# Power-Supplies.net
KiCad netlist of a schematic drawn in Altium Designer
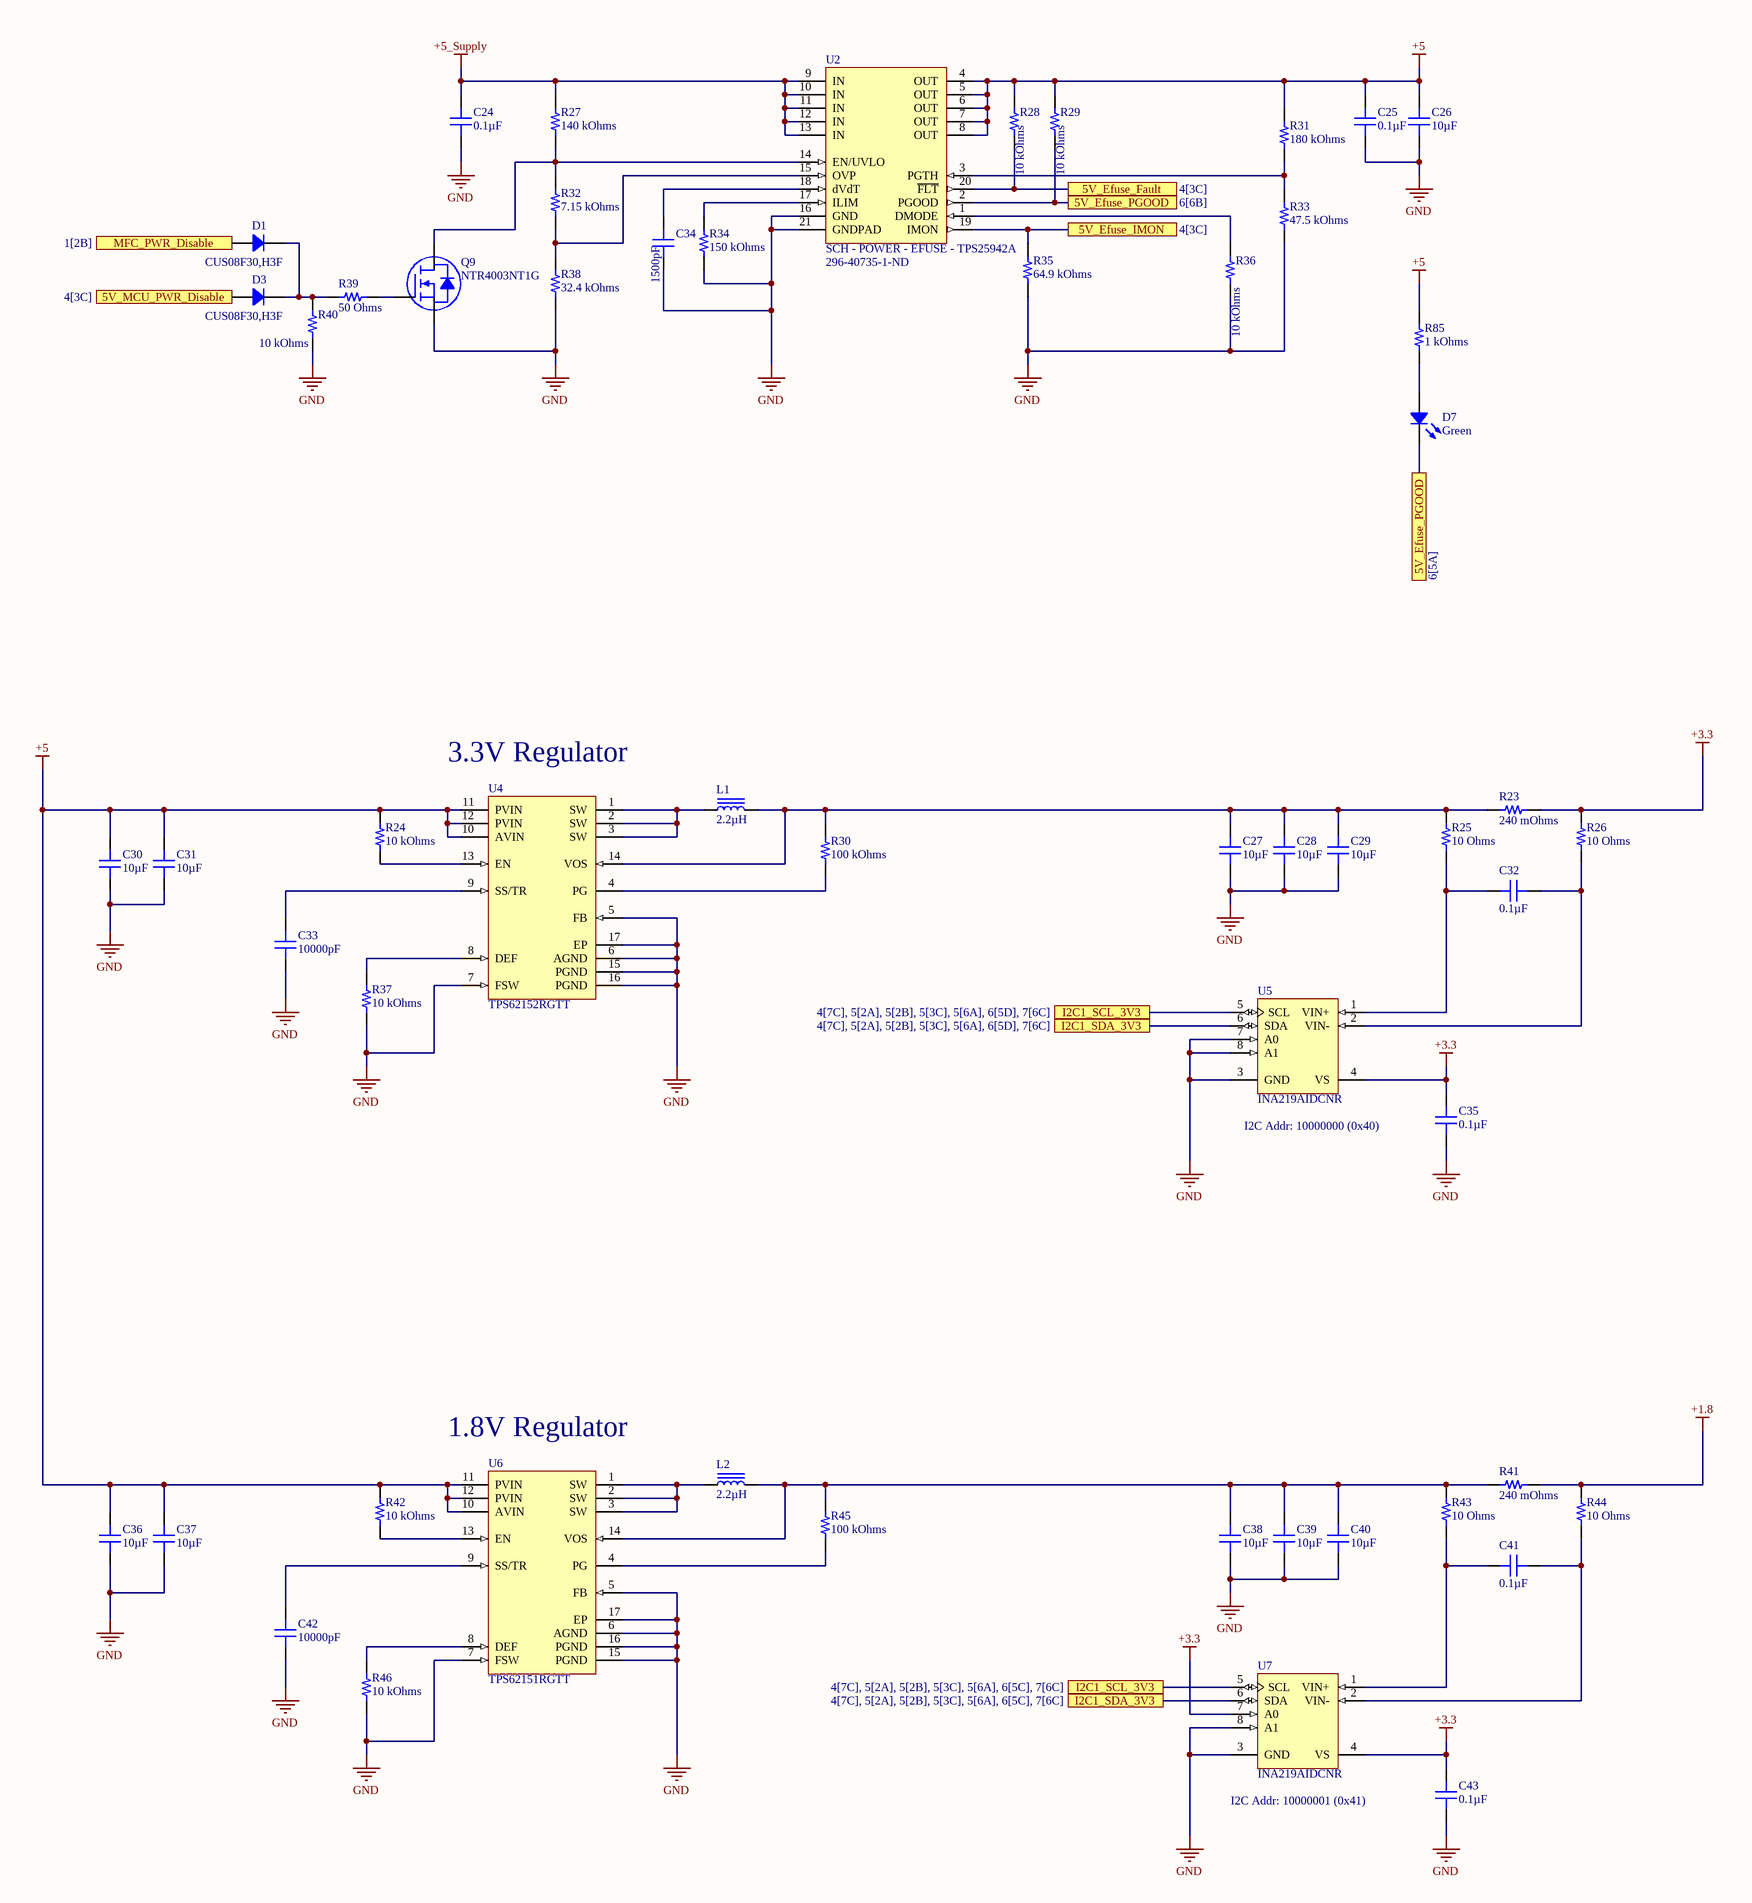
[diagram p0: Power-Supplies.SchDoc]

(export (version "E")
  (design (tool "Eeschema 10.0.6"))
  (components
    (comp (ref "C24")
      (value "0.1µF")
      (footprint "CAP 0603_1608")
      (description "CAP CER 0.1UF 25V X7R 0603")
      (fields
        (field (name "PART NUMBER") "CL10B104KA8WPNC")
        (field (name "MANUFACTURER") "Samsung Electro-Mechanics")
      )
      (libsource (lib "Celestial Altium Library - altium_library") (part "Capacitor"))
    )
    (comp (ref "C25")
      (value "0.1µF")
      (footprint "CAP 0603_1608")
      (description "CAP CER 0.1UF 25V X7R 0603")
      (fields
        (field (name "PART NUMBER") "CL10B104KA8WPNC")
        (field (name "MANUFACTURER") "Samsung Electro-Mechanics")
      )
      (libsource (lib "Celestial Altium Library - altium_library") (part "Capacitor"))
    )
    (comp (ref "C26")
      (value "10µF")
      (footprint "CAP 0805_2012")
      (description "CAP CER 10UF 16V X5R 0805")
      (fields (field (name "PART NUMBER") "CC0805KKX5R7BB106") (field (name "MANUFACTURER") "Yageo"))
      (libsource (lib "Celestial Altium Library - altium_library") (part "Capacitor"))
    )
    (comp (ref "C27")
      (value "10µF")
      (footprint "CAP 0805_2012")
      (description "CAP CER 10UF 16V X5R 0805")
      (fields (field (name "PART NUMBER") "CC0805KKX5R7BB106") (field (name "MANUFACTURER") "Yageo"))
      (libsource (lib "Celestial Altium Library - altium_library") (part "Capacitor"))
    )
    (comp (ref "C28")
      (value "10µF")
      (footprint "CAP 0805_2012")
      (description "CAP CER 10UF 16V X5R 0805")
      (fields (field (name "PART NUMBER") "CC0805KKX5R7BB106") (field (name "MANUFACTURER") "Yageo"))
      (libsource (lib "Celestial Altium Library - altium_library") (part "Capacitor"))
    )
    (comp (ref "C29")
      (value "10µF")
      (footprint "CAP 0805_2012")
      (description "CAP CER 10UF 16V X5R 0805")
      (fields (field (name "PART NUMBER") "CC0805KKX5R7BB106") (field (name "MANUFACTURER") "Yageo"))
      (libsource (lib "Celestial Altium Library - altium_library") (part "Capacitor"))
    )
    (comp (ref "C30")
      (value "10µF")
      (footprint "CAP 0805_2012")
      (description "CAP CER 10UF 16V X5R 0805")
      (fields (field (name "PART NUMBER") "CC0805KKX5R7BB106") (field (name "MANUFACTURER") "Yageo"))
      (libsource (lib "Celestial Altium Library - altium_library") (part "Capacitor"))
    )
    (comp (ref "C31")
      (value "10µF")
      (footprint "CAP 0805_2012")
      (description "CAP CER 10UF 16V X5R 0805")
      (fields (field (name "PART NUMBER") "CC0805KKX5R7BB106") (field (name "MANUFACTURER") "Yageo"))
      (libsource (lib "Celestial Altium Library - altium_library") (part "Capacitor"))
    )
    (comp (ref "C32")
      (value "0.1µF")
      (footprint "CAP 0603_1608")
      (description "CAP CER 0.1UF 25V X7R 0603")
      (fields
        (field (name "PART NUMBER") "CL10B104KA8WPNC")
        (field (name "MANUFACTURER") "Samsung Electro-Mechanics")
      )
      (libsource (lib "Celestial Altium Library - altium_library") (part "Capacitor"))
    )
    (comp (ref "C33")
      (value "10000pF")
      (footprint "CAP 0603_1608")
      (description "CAP CER 10000PF 16V X7R 0603")
      (fields (field (name "PART NUMBER") "C0603S103K4RACTU") (field (name "MANUFACTURER") "KEMET"))
      (libsource (lib "Celestial Altium Library - altium_library") (part "Capacitor"))
    )
    (comp (ref "C34")
      (value "1500pF")
      (footprint "CAP 0603_1608")
      (description "CAP CER 1500PF 25V X7R 0603")
      (fields (field (name "PART NUMBER") "CC0603JRX7R8BB152") (field (name "MANUFACTURER") "Yageo"))
      (libsource (lib "Celestial Altium Library - altium_library") (part "Capacitor"))
    )
    (comp (ref "C35")
      (value "0.1µF")
      (footprint "CAP 0603_1608")
      (description "CAP CER 0.1UF 25V X7R 0603")
      (fields
        (field (name "PART NUMBER") "CL10B104KA8WPNC")
        (field (name "MANUFACTURER") "Samsung Electro-Mechanics")
      )
      (libsource (lib "Celestial Altium Library - altium_library") (part "Capacitor"))
    )
    (comp (ref "C36")
      (value "10µF")
      (footprint "CAP 0805_2012")
      (description "CAP CER 10UF 16V X5R 0805")
      (fields (field (name "PART NUMBER") "CC0805KKX5R7BB106") (field (name "MANUFACTURER") "Yageo"))
      (libsource (lib "Celestial Altium Library - altium_library") (part "Capacitor"))
    )
    (comp (ref "C37")
      (value "10µF")
      (footprint "CAP 0805_2012")
      (description "CAP CER 10UF 16V X5R 0805")
      (fields (field (name "PART NUMBER") "CC0805KKX5R7BB106") (field (name "MANUFACTURER") "Yageo"))
      (libsource (lib "Celestial Altium Library - altium_library") (part "Capacitor"))
    )
    (comp (ref "C38")
      (value "10µF")
      (footprint "CAP 0805_2012")
      (description "CAP CER 10UF 16V X5R 0805")
      (fields (field (name "PART NUMBER") "CC0805KKX5R7BB106") (field (name "MANUFACTURER") "Yageo"))
      (libsource (lib "Celestial Altium Library - altium_library") (part "Capacitor"))
    )
    (comp (ref "C39")
      (value "10µF")
      (footprint "CAP 0805_2012")
      (description "CAP CER 10UF 16V X5R 0805")
      (fields (field (name "PART NUMBER") "CC0805KKX5R7BB106") (field (name "MANUFACTURER") "Yageo"))
      (libsource (lib "Celestial Altium Library - altium_library") (part "Capacitor"))
    )
    (comp (ref "C40")
      (value "10µF")
      (footprint "CAP 0805_2012")
      (description "CAP CER 10UF 16V X5R 0805")
      (fields (field (name "PART NUMBER") "CC0805KKX5R7BB106") (field (name "MANUFACTURER") "Yageo"))
      (libsource (lib "Celestial Altium Library - altium_library") (part "Capacitor"))
    )
    (comp (ref "C41")
      (value "0.1µF")
      (footprint "CAP 0603_1608")
      (description "CAP CER 0.1UF 25V X7R 0603")
      (fields
        (field (name "PART NUMBER") "CL10B104KA8WPNC")
        (field (name "MANUFACTURER") "Samsung Electro-Mechanics")
      )
      (libsource (lib "Celestial Altium Library - altium_library") (part "Capacitor"))
    )
    (comp (ref "C42")
      (value "10000pF")
      (footprint "CAP 0603_1608")
      (description "CAP CER 10000PF 16V X7R 0603")
      (fields (field (name "PART NUMBER") "C0603S103K4RACTU") (field (name "MANUFACTURER") "KEMET"))
      (libsource (lib "Celestial Altium Library - altium_library") (part "Capacitor"))
    )
    (comp (ref "C43")
      (value "0.1µF")
      (footprint "CAP 0603_1608")
      (description "CAP CER 0.1UF 25V X7R 0603")
      (fields
        (field (name "PART NUMBER") "CL10B104KA8WPNC")
        (field (name "MANUFACTURER") "Samsung Electro-Mechanics")
      )
      (libsource (lib "Celestial Altium Library - altium_library") (part "Capacitor"))
    )
    (comp (ref "D1")
      (value "CUS08F30,H3F")
      (footprint "SOD323")
      (description "DIODE SCHOTTKY 30V 800MA USC")
      (fields (field (name "MANUFACTURER") "Toshiba Semiconductor and Storage"))
      (libsource (lib "Celestial Altium Library - altium_library") (part "Diode"))
    )
    (comp (ref "D3")
      (value "CUS08F30,H3F")
      (footprint "SOD323")
      (description "DIODE SCHOTTKY 30V 800MA USC")
      (fields (field (name "MANUFACTURER") "Toshiba Semiconductor and Storage"))
      (libsource (lib "Celestial Altium Library - altium_library") (part "Diode"))
    )
    (comp (ref "D7")
      (value "Green")
      (footprint "LED 0603_1608 GREEN")
      (description "LED GREEN CLEAR CHIP SMD")
      (fields (field (name "PART NUMBER") "LTST-C193KGKT-5A") (field (name "MANUFACTURER") "Lite-On Inc."))
      (libsource (lib "Celestial Altium Library - altium_library") (part "LED"))
    )
    (comp (ref "L1")
      (value "2.2µH")
      (footprint "BOURNS SRN4018")
      (description "FIXED IND 2.2UH 2.9A 44 MOHM SMD")
      (fields (field (name "PART NUMBER") "SRN4018-2R2M") (field (name "MANUFACTURER") "Bourns Inc."))
      (libsource (lib "Celestial Altium Library - altium_library") (part "Inductor"))
    )
    (comp (ref "L2")
      (value "2.2µH")
      (footprint "BOURNS SRN4018")
      (description "FIXED IND 2.2UH 2.9A 44 MOHM SMD")
      (fields (field (name "PART NUMBER") "SRN4018-2R2M") (field (name "MANUFACTURER") "Bourns Inc."))
      (libsource (lib "Celestial Altium Library - altium_library") (part "Inductor"))
    )
    (comp (ref "Q9")
      (value "NTR4003NT1G")
      (footprint "ON SEMI SOT-23-3")
      (description "MOSFET N-CH 30V 500MA SOT-23")
      (fields (field (name "MANUFACTURER") "ON Semiconductor"))
      (libsource (lib "Celestial Altium Library - altium_library") (part "ON SEMI MOSFET N-CH SOT-23-3"))
    )
    (comp (ref "R23")
      (value "240 mOhms")
      (footprint "RES 0805_2012")
      (description "RES 0.24 OHM 1% 1/2W 0805")
      (fields
        (field (name "PART NUMBER") "ERJ-6DQFR24V")
        (field (name "MANUFACTURER") "Panasonic Electronic Components")
      )
      (libsource (lib "Celestial Altium Library - altium_library") (part "Resistor"))
    )
    (comp (ref "R24")
      (value "10 kOhms")
      (footprint "RES 0603_1608")
      (description "RES 10K OHM 5% 1/10W 0603")
      (fields
        (field (name "PART NUMBER") "RMCF0603JT10K0")
        (field (name "MANUFACTURER") "Stackpole Electronics Inc")
      )
      (libsource (lib "Celestial Altium Library - altium_library") (part "Resistor"))
    )
    (comp (ref "R25")
      (value "10 Ohms")
      (footprint "RES 0603_1608")
      (description "CRGCQ 0603 10R 1%")
      (fields
        (field (name "PART NUMBER") "CRGCQ0603F10R")
        (field (name "MANUFACTURER") "TE Connectivity Passive Product")
      )
      (libsource (lib "Celestial Altium Library - altium_library") (part "Resistor"))
    )
    (comp (ref "R26")
      (value "10 Ohms")
      (footprint "RES 0603_1608")
      (description "CRGCQ 0603 10R 1%")
      (fields
        (field (name "PART NUMBER") "CRGCQ0603F10R")
        (field (name "MANUFACTURER") "TE Connectivity Passive Product")
      )
      (libsource (lib "Celestial Altium Library - altium_library") (part "Resistor"))
    )
    (comp (ref "R27")
      (value "140 kOhms")
      (footprint "RES 0603_1608")
      (description "RES SMD 140K OHM 0.1% 1/10W 0603")
      (fields (field (name "PART NUMBER") "RT0603BRE07140KL") (field (name "MANUFACTURER") "Yageo"))
      (libsource (lib "Celestial Altium Library - altium_library") (part "Resistor"))
    )
    (comp (ref "R28")
      (value "10 kOhms")
      (footprint "RES 0603_1608")
      (description "RES 10K OHM 5% 1/10W 0603")
      (fields
        (field (name "PART NUMBER") "RMCF0603JT10K0")
        (field (name "MANUFACTURER") "Stackpole Electronics Inc")
      )
      (libsource (lib "Celestial Altium Library - altium_library") (part "Resistor"))
    )
    (comp (ref "R29")
      (value "10 kOhms")
      (footprint "RES 0603_1608")
      (description "RES 10K OHM 5% 1/10W 0603")
      (fields
        (field (name "PART NUMBER") "RMCF0603JT10K0")
        (field (name "MANUFACTURER") "Stackpole Electronics Inc")
      )
      (libsource (lib "Celestial Altium Library - altium_library") (part "Resistor"))
    )
    (comp (ref "R30")
      (value "100 kOhms")
      (footprint "RES 0603_1608")
      (description "RES SMD 100K OHM 5% 1/10W 0603")
      (fields (field (name "PART NUMBER") "RC0603JR-10100KL") (field (name "MANUFACTURER") "Yageo"))
      (libsource (lib "Celestial Altium Library - altium_library") (part "Resistor"))
    )
    (comp (ref "R31")
      (value "180 kOhms")
      (footprint "RES 0603_1608")
      (description "RES 180K OHM 1% 1/10W 0603")
      (fields
        (field (name "PART NUMBER") "RMCF0603FT180K")
        (field (name "MANUFACTURER") "Stackpole Electronics Inc")
      )
      (libsource (lib "Celestial Altium Library - altium_library") (part "Resistor"))
    )
    (comp (ref "R32")
      (value "7.15 kOhms")
      (footprint "RES 0603_1608")
      (description "RES SMD 7.15K OHM 0.1% 1/5W 0603")
      (fields
        (field (name "PART NUMBER") "ERJ-PB3B7151V")
        (field (name "MANUFACTURER") "Panasonic Electronic Components")
      )
      (libsource (lib "Celestial Altium Library - altium_library") (part "Resistor"))
    )
    (comp (ref "R33")
      (value "47.5 kOhms")
      (footprint "RES 0603_1608")
      (description "RES 47.5K OHM 1% 1/10W 0603")
      (fields
        (field (name "PART NUMBER") "RMCF0603FG47K5")
        (field (name "MANUFACTURER") "Stackpole Electronics Inc")
      )
      (libsource (lib "Celestial Altium Library - altium_library") (part "Resistor"))
    )
    (comp (ref "R34")
      (value "150 kOhms")
      (footprint "RES 0603_1608")
      (description "RES 150K OHM 1% 1/10W 0603")
      (fields
        (field (name "PART NUMBER") "RMCF0603FG150K")
        (field (name "MANUFACTURER") "Stackpole Electronics Inc")
      )
      (libsource (lib "Celestial Altium Library - altium_library") (part "Resistor"))
    )
    (comp (ref "R35")
      (value "64.9 kOhms")
      (footprint "RES 0603_1608")
      (description "RES 64.9K OHM 1% 1/10W 0603")
      (fields
        (field (name "PART NUMBER") "RMCF0603FT64K9")
        (field (name "MANUFACTURER") "Stackpole Electronics Inc")
      )
      (libsource (lib "Celestial Altium Library - altium_library") (part "Resistor"))
    )
    (comp (ref "R36")
      (value "10 kOhms")
      (footprint "RES 0603_1608")
      (description "RES 10K OHM 5% 1/10W 0603")
      (fields
        (field (name "PART NUMBER") "RMCF0603JT10K0")
        (field (name "MANUFACTURER") "Stackpole Electronics Inc")
      )
      (libsource (lib "Celestial Altium Library - altium_library") (part "Resistor"))
    )
    (comp (ref "R37")
      (value "10 kOhms")
      (footprint "RES 0603_1608")
      (description "RES 10K OHM 5% 1/10W 0603")
      (fields
        (field (name "PART NUMBER") "RMCF0603JT10K0")
        (field (name "MANUFACTURER") "Stackpole Electronics Inc")
      )
      (libsource (lib "Celestial Altium Library - altium_library") (part "Resistor"))
    )
    (comp (ref "R38")
      (value "32.4 kOhms")
      (footprint "RES 0603_1608")
      (description "RES SMD 32.4K OHM 0.1% 1/5W 0603")
      (fields
        (field (name "PART NUMBER") "ERJ-PB3B3242V")
        (field (name "MANUFACTURER") "Panasonic Electronic Components")
      )
      (libsource (lib "Celestial Altium Library - altium_library") (part "Resistor"))
    )
    (comp (ref "R39")
      (value "50 Ohms")
      (footprint "RES 0603_1608")
      (description "RES SMD 50 OHM 1% 1/10W 0603")
      (fields (field (name "PART NUMBER") "CRCW060350R0FKEA") (field (name "MANUFACTURER") "Vishay Dale"))
      (libsource (lib "Celestial Altium Library - altium_library") (part "Resistor"))
    )
    (comp (ref "R40")
      (value "10 kOhms")
      (footprint "RES 0603_1608")
      (description "RES 10K OHM 5% 1/10W 0603")
      (fields
        (field (name "PART NUMBER") "RMCF0603JT10K0")
        (field (name "MANUFACTURER") "Stackpole Electronics Inc")
      )
      (libsource (lib "Celestial Altium Library - altium_library") (part "Resistor"))
    )
    (comp (ref "R41")
      (value "240 mOhms")
      (footprint "RES 0805_2012")
      (description "RES 0.24 OHM 1% 1/2W 0805")
      (fields
        (field (name "PART NUMBER") "ERJ-6DQFR24V")
        (field (name "MANUFACTURER") "Panasonic Electronic Components")
      )
      (libsource (lib "Celestial Altium Library - altium_library") (part "Resistor"))
    )
    (comp (ref "R42")
      (value "10 kOhms")
      (footprint "RES 0603_1608")
      (description "RES 10K OHM 5% 1/10W 0603")
      (fields
        (field (name "PART NUMBER") "RMCF0603JT10K0")
        (field (name "MANUFACTURER") "Stackpole Electronics Inc")
      )
      (libsource (lib "Celestial Altium Library - altium_library") (part "Resistor"))
    )
    (comp (ref "R43")
      (value "10 Ohms")
      (footprint "RES 0603_1608")
      (description "CRGCQ 0603 10R 1%")
      (fields
        (field (name "PART NUMBER") "CRGCQ0603F10R")
        (field (name "MANUFACTURER") "TE Connectivity Passive Product")
      )
      (libsource (lib "Celestial Altium Library - altium_library") (part "Resistor"))
    )
    (comp (ref "R44")
      (value "10 Ohms")
      (footprint "RES 0603_1608")
      (description "CRGCQ 0603 10R 1%")
      (fields
        (field (name "PART NUMBER") "CRGCQ0603F10R")
        (field (name "MANUFACTURER") "TE Connectivity Passive Product")
      )
      (libsource (lib "Celestial Altium Library - altium_library") (part "Resistor"))
    )
    (comp (ref "R45")
      (value "100 kOhms")
      (footprint "RES 0603_1608")
      (description "RES SMD 100K OHM 5% 1/10W 0603")
      (fields (field (name "PART NUMBER") "RC0603JR-10100KL") (field (name "MANUFACTURER") "Yageo"))
      (libsource (lib "Celestial Altium Library - altium_library") (part "Resistor"))
    )
    (comp (ref "R46")
      (value "10 kOhms")
      (footprint "RES 0603_1608")
      (description "RES 10K OHM 5% 1/10W 0603")
      (fields
        (field (name "PART NUMBER") "RMCF0603JT10K0")
        (field (name "MANUFACTURER") "Stackpole Electronics Inc")
      )
      (libsource (lib "Celestial Altium Library - altium_library") (part "Resistor"))
    )
    (comp (ref "R85")
      (value "1 kOhms")
      (footprint "RES 0603_1608")
      (description "RES 1K OHM 1% 1/8W 0603")
      (fields
        (field (name "PART NUMBER") "RNCP0603FTD1K00")
        (field (name "MANUFACTURER") "Stackpole Electronics Inc")
      )
      (libsource (lib "Celestial Altium Library - altium_library") (part "Resistor"))
    )
    (comp (ref "U2")
      (value "SCH - POWER - EFUSE - TPS25942A")
      (footprint "PCB - LEADLESS - QFN - TI 20-WQFN")
      (fields (field (name "SUPPLIER PART NUMBER 1") "296-40735-1-ND"))
      (libsource (lib "HAB_ICs") (part "SCH - POWER - EFUSE - TPS25942A"))
    )
    (comp (ref "U4")
      (value "TPS62152RGTT")
      (footprint "RGT0016C_V")
      (fields (field (name "MANUFACTURER") "Texas Instruments"))
      (libsource (lib "Altium Content Vault") (part "TI-TPS62152RGT16-1700X1700TP"))
    )
    (comp (ref "U5")
      (value "INA219AIDCNR")
      (footprint "DCN0008A_M")
      (fields (field (name "MANUFACTURER") "Texas Instruments"))
      (libsource (lib "Altium Content Vault") (part "TI-INA219DCN8"))
    )
    (comp (ref "U6")
      (value "TPS62151RGTT")
      (footprint "RGT0016C_V")
      (fields (field (name "MANUFACTURER") "Texas Instruments"))
      (libsource (lib "Altium Content Vault") (part "TI-TPS62151RGT16-1700X1700TP"))
    )
    (comp (ref "U7")
      (value "INA219AIDCNR")
      (footprint "DCN0008A_M")
      (fields (field (name "MANUFACTURER") "Texas Instruments"))
      (libsource (lib "Altium Content Vault") (part "TI-INA219DCN8"))
    )
  )
  (nets
    (net (code "1") (name "+1.8") (class "Default")
      (node (ref "R41") (pin "2") (pinfunction "2_2") (pintype "passive"))
      (node (ref "R44") (pin "2") (pinfunction "2_2") (pintype "passive"))
    )
    (net (code "2") (name "+3.3") (class "Default")
      (node (ref "C35") (pin "2") (pinfunction "2_2") (pintype "passive"))
      (node (ref "C43") (pin "2") (pinfunction "2_2") (pintype "passive"))
      (node (ref "R23") (pin "2") (pinfunction "2_2") (pintype "passive"))
      (node (ref "R26") (pin "2") (pinfunction "2_2") (pintype "passive"))
      (node (ref "U5") (pin "4") (pinfunction "VS_4") (pintype "power_in"))
      (node (ref "U7") (pin "4") (pinfunction "VS_4") (pintype "power_in"))
      (node (ref "U7") (pin "7") (pinfunction "A0_7") (pintype "input"))
    )
    (net (code "3") (name "+5") (class "Default")
      (node (ref "C25") (pin "2") (pinfunction "2_2") (pintype "passive"))
      (node (ref "C26") (pin "2") (pinfunction "2_2") (pintype "passive"))
      (node (ref "C30") (pin "2") (pinfunction "2_2") (pintype "passive"))
      (node (ref "C31") (pin "2") (pinfunction "2_2") (pintype "passive"))
      (node (ref "C36") (pin "2") (pinfunction "2_2") (pintype "passive"))
      (node (ref "C37") (pin "2") (pinfunction "2_2") (pintype "passive"))
      (node (ref "R24") (pin "2") (pinfunction "2_2") (pintype "passive"))
      (node (ref "R28") (pin "2") (pinfunction "2_2") (pintype "passive"))
      (node (ref "R29") (pin "2") (pinfunction "2_2") (pintype "passive"))
      (node (ref "R31") (pin "2") (pinfunction "2_2") (pintype "passive"))
      (node (ref "R42") (pin "2") (pinfunction "2_2") (pintype "passive"))
      (node (ref "R85") (pin "1") (pinfunction "1_1") (pintype "passive"))
      (node (ref "U2") (pin "4") (pinfunction "OUT_4") (pintype "power_in"))
      (node (ref "U2") (pin "5") (pinfunction "OUT_5") (pintype "power_in"))
      (node (ref "U2") (pin "6") (pinfunction "OUT_6") (pintype "power_in"))
      (node (ref "U2") (pin "7") (pinfunction "OUT_7") (pintype "power_in"))
      (node (ref "U2") (pin "8") (pinfunction "OUT_8") (pintype "power_in"))
      (node (ref "U4") (pin "10") (pinfunction "AVIN_10") (pintype "power_in"))
      (node (ref "U4") (pin "11") (pinfunction "PVIN_11") (pintype "power_in"))
      (node (ref "U4") (pin "12") (pinfunction "PVIN_12") (pintype "power_in"))
      (node (ref "U6") (pin "10") (pinfunction "AVIN_10") (pintype "power_in"))
      (node (ref "U6") (pin "11") (pinfunction "PVIN_11") (pintype "power_in"))
      (node (ref "U6") (pin "12") (pinfunction "PVIN_12") (pintype "power_in"))
    )
    (net (code "4") (name "+5_Supply") (class "Default")
      (node (ref "C24") (pin "2") (pinfunction "2_2") (pintype "passive"))
      (node (ref "R27") (pin "2") (pinfunction "2_2") (pintype "passive"))
      (node (ref "U2") (pin "10") (pinfunction "IN_10") (pintype "power_in"))
      (node (ref "U2") (pin "11") (pinfunction "IN_11") (pintype "power_in"))
      (node (ref "U2") (pin "12") (pinfunction "IN_12") (pintype "power_in"))
      (node (ref "U2") (pin "13") (pinfunction "IN_13") (pintype "power_in"))
      (node (ref "U2") (pin "9") (pinfunction "IN_9") (pintype "power_in"))
    )
    (net (code "5") (name "/5V_Efuse_Fault") (class "Default")
      (node (ref "R28") (pin "1") (pinfunction "1_1") (pintype "passive"))
      (node (ref "U2") (pin "20") (pinfunction "~{FLT}_20") (pintype "output"))
    )
    (net (code "6") (name "/5V_Efuse_IMON") (class "Default")
      (node (ref "R35") (pin "2") (pinfunction "2_2") (pintype "passive"))
      (node (ref "U2") (pin "19") (pinfunction "IMON_19") (pintype "output"))
    )
    (net (code "7") (name "/5V_Efuse_PGOOD") (class "Default")
      (node (ref "D7") (pin "2") (pinfunction "2_2") (pintype "passive"))
      (node (ref "R29") (pin "1") (pinfunction "1_1") (pintype "passive"))
      (node (ref "U2") (pin "2") (pinfunction "PGOOD_2") (pintype "output"))
    )
    (net (code "8") (name "/5V_MCU_PWR_Disable") (class "Default")
      (node (ref "D3") (pin "1") (pinfunction "1_1") (pintype "passive"))
    )
    (net (code "9") (name "/I2C1_SCL_3V3") (class "Default")
      (node (ref "U5") (pin "5") (pinfunction "SCL_5") (pintype "bidirectional"))
      (node (ref "U7") (pin "5") (pinfunction "SCL_5") (pintype "bidirectional"))
    )
    (net (code "10") (name "/I2C1_SDA_3V3") (class "Default")
      (node (ref "U5") (pin "6") (pinfunction "SDA_6") (pintype "bidirectional"))
      (node (ref "U7") (pin "6") (pinfunction "SDA_6") (pintype "bidirectional"))
    )
    (net (code "11") (name "/MFC_PWR_Disable") (class "Default")
      (node (ref "D1") (pin "1") (pinfunction "1_1") (pintype "passive"))
    )
    (net (code "12") (name "GND") (class "Default")
      (node (ref "C24") (pin "1") (pinfunction "1_1") (pintype "passive"))
      (node (ref "C25") (pin "1") (pinfunction "1_1") (pintype "passive"))
      (node (ref "C26") (pin "1") (pinfunction "1_1") (pintype "passive"))
      (node (ref "C27") (pin "1") (pinfunction "1_1") (pintype "passive"))
      (node (ref "C28") (pin "1") (pinfunction "1_1") (pintype "passive"))
      (node (ref "C29") (pin "1") (pinfunction "1_1") (pintype "passive"))
      (node (ref "C30") (pin "1") (pinfunction "1_1") (pintype "passive"))
      (node (ref "C31") (pin "1") (pinfunction "1_1") (pintype "passive"))
      (node (ref "C33") (pin "1") (pinfunction "1_1") (pintype "passive"))
      (node (ref "C34") (pin "1") (pinfunction "1_1") (pintype "passive"))
      (node (ref "C35") (pin "1") (pinfunction "1_1") (pintype "passive"))
      (node (ref "C36") (pin "1") (pinfunction "1_1") (pintype "passive"))
      (node (ref "C37") (pin "1") (pinfunction "1_1") (pintype "passive"))
      (node (ref "C38") (pin "1") (pinfunction "1_1") (pintype "passive"))
      (node (ref "C39") (pin "1") (pinfunction "1_1") (pintype "passive"))
      (node (ref "C40") (pin "1") (pinfunction "1_1") (pintype "passive"))
      (node (ref "C42") (pin "1") (pinfunction "1_1") (pintype "passive"))
      (node (ref "C43") (pin "1") (pinfunction "1_1") (pintype "passive"))
      (node (ref "Q9") (pin "2") (pinfunction "S_2") (pintype "passive"))
      (node (ref "R33") (pin "1") (pinfunction "1_1") (pintype "passive"))
      (node (ref "R34") (pin "1") (pinfunction "1_1") (pintype "passive"))
      (node (ref "R35") (pin "1") (pinfunction "1_1") (pintype "passive"))
      (node (ref "R36") (pin "1") (pinfunction "1_1") (pintype "passive"))
      (node (ref "R37") (pin "1") (pinfunction "1_1") (pintype "passive"))
      (node (ref "R38") (pin "1") (pinfunction "1_1") (pintype "passive"))
      (node (ref "R40") (pin "1") (pinfunction "1_1") (pintype "passive"))
      (node (ref "R46") (pin "1") (pinfunction "1_1") (pintype "passive"))
      (node (ref "U2") (pin "16") (pinfunction "GND_16") (pintype "power_in"))
      (node (ref "U2") (pin "21") (pinfunction "GNDPAD_21") (pintype "power_in"))
      (node (ref "U4") (pin "15") (pinfunction "PGND_15") (pintype "power_in"))
      (node (ref "U4") (pin "16") (pinfunction "PGND_16") (pintype "power_in"))
      (node (ref "U4") (pin "17") (pinfunction "EP_17") (pintype "power_in"))
      (node (ref "U4") (pin "5") (pinfunction "FB_5") (pintype "input"))
      (node (ref "U4") (pin "6") (pinfunction "AGND_6") (pintype "power_in"))
      (node (ref "U4") (pin "7") (pinfunction "FSW_7") (pintype "input"))
      (node (ref "U5") (pin "3") (pinfunction "GND_3") (pintype "power_in"))
      (node (ref "U5") (pin "7") (pinfunction "A0_7") (pintype "input"))
      (node (ref "U5") (pin "8") (pinfunction "A1_8") (pintype "input"))
      (node (ref "U6") (pin "15") (pinfunction "PGND_15") (pintype "power_in"))
      (node (ref "U6") (pin "16") (pinfunction "PGND_16") (pintype "power_in"))
      (node (ref "U6") (pin "17") (pinfunction "EP_17") (pintype "power_in"))
      (node (ref "U6") (pin "5") (pinfunction "FB_5") (pintype "input"))
      (node (ref "U6") (pin "6") (pinfunction "AGND_6") (pintype "power_in"))
      (node (ref "U6") (pin "7") (pinfunction "FSW_7") (pintype "input"))
      (node (ref "U7") (pin "3") (pinfunction "GND_3") (pintype "power_in"))
      (node (ref "U7") (pin "8") (pinfunction "A1_8") (pintype "input"))
    )
    (net (code "13") (name "Net-(D1-Pad2)") (class "Default")
      (node (ref "D1") (pin "2") (pinfunction "2_2") (pintype "passive"))
      (node (ref "D3") (pin "2") (pinfunction "2_2") (pintype "passive"))
      (node (ref "R39") (pin "2") (pinfunction "2_2") (pintype "passive"))
      (node (ref "R40") (pin "2") (pinfunction "2_2") (pintype "passive"))
    )
    (net (code "14") (name "Net-(D7-Pad1)") (class "Default")
      (node (ref "D7") (pin "1") (pinfunction "1_1") (pintype "passive"))
      (node (ref "R85") (pin "2") (pinfunction "2_2") (pintype "passive"))
    )
    (net (code "15") (name "Net-(L1-Pad1)") (class "Default")
      (node (ref "L1") (pin "1") (pinfunction "1_1") (pintype "passive"))
      (node (ref "U4") (pin "1") (pinfunction "SW_1") (pintype "power_in"))
      (node (ref "U4") (pin "2") (pinfunction "SW_2") (pintype "power_in"))
      (node (ref "U4") (pin "3") (pinfunction "SW_3") (pintype "power_in"))
    )
    (net (code "16") (name "Net-(L2-Pad1)") (class "Default")
      (node (ref "L2") (pin "1") (pinfunction "1_1") (pintype "passive"))
      (node (ref "U6") (pin "1") (pinfunction "SW_1") (pintype "power_in"))
      (node (ref "U6") (pin "2") (pinfunction "SW_2") (pintype "power_in"))
      (node (ref "U6") (pin "3") (pinfunction "SW_3") (pintype "power_in"))
    )
    (net (code "17") (name "Net-(Q9-D)") (class "Default")
      (node (ref "Q9") (pin "3") (pinfunction "D_3") (pintype "passive"))
      (node (ref "R27") (pin "1") (pinfunction "1_1") (pintype "passive"))
      (node (ref "R32") (pin "2") (pinfunction "2_2") (pintype "passive"))
      (node (ref "U2") (pin "14") (pinfunction "EN/UVLO_14") (pintype "input"))
    )
    (net (code "18") (name "Net-(Q9-G)") (class "Default")
      (node (ref "Q9") (pin "1") (pinfunction "G_1") (pintype "passive"))
      (node (ref "R39") (pin "1") (pinfunction "1_1") (pintype "passive"))
    )
    (net (code "19") (name "Net-(U2-DMODE)") (class "Default")
      (node (ref "R36") (pin "2") (pinfunction "2_2") (pintype "passive"))
      (node (ref "U2") (pin "1") (pinfunction "DMODE_1") (pintype "input"))
    )
    (net (code "20") (name "Net-(U2-ILIM)") (class "Default")
      (node (ref "R34") (pin "2") (pinfunction "2_2") (pintype "passive"))
      (node (ref "U2") (pin "17") (pinfunction "ILIM_17") (pintype "input"))
    )
    (net (code "21") (name "Net-(U2-OVP)") (class "Default")
      (node (ref "R32") (pin "1") (pinfunction "1_1") (pintype "passive"))
      (node (ref "R38") (pin "2") (pinfunction "2_2") (pintype "passive"))
      (node (ref "U2") (pin "15") (pinfunction "OVP_15") (pintype "input"))
    )
    (net (code "22") (name "Net-(U2-PGTH)") (class "Default")
      (node (ref "R31") (pin "1") (pinfunction "1_1") (pintype "passive"))
      (node (ref "R33") (pin "2") (pinfunction "2_2") (pintype "passive"))
      (node (ref "U2") (pin "3") (pinfunction "PGTH_3") (pintype "input"))
    )
    (net (code "23") (name "Net-(U2-dVdT)") (class "Default")
      (node (ref "C34") (pin "2") (pinfunction "2_2") (pintype "passive"))
      (node (ref "U2") (pin "18") (pinfunction "dVdT_18") (pintype "input"))
    )
    (net (code "24") (name "Net-(U4-DEF)") (class "Default")
      (node (ref "R37") (pin "2") (pinfunction "2_2") (pintype "passive"))
      (node (ref "U4") (pin "8") (pinfunction "DEF_8") (pintype "input"))
    )
    (net (code "25") (name "Net-(U4-EN)") (class "Default")
      (node (ref "R24") (pin "1") (pinfunction "1_1") (pintype "passive"))
      (node (ref "U4") (pin "13") (pinfunction "EN_13") (pintype "input"))
    )
    (net (code "26") (name "Net-(U4-PG)") (class "Default")
      (node (ref "R30") (pin "1") (pinfunction "1_1") (pintype "passive"))
      (node (ref "U4") (pin "4") (pinfunction "PG_4") (pintype "tri_state"))
    )
    (net (code "27") (name "Net-(U4-SS{slash}TR)") (class "Default")
      (node (ref "C33") (pin "2") (pinfunction "2_2") (pintype "passive"))
      (node (ref "U4") (pin "9") (pinfunction "SS/TR_9") (pintype "input"))
    )
    (net (code "28") (name "Net-(U4-VOS)") (class "Default")
      (node (ref "C27") (pin "2") (pinfunction "2_2") (pintype "passive"))
      (node (ref "C28") (pin "2") (pinfunction "2_2") (pintype "passive"))
      (node (ref "C29") (pin "2") (pinfunction "2_2") (pintype "passive"))
      (node (ref "L1") (pin "2") (pinfunction "2_2") (pintype "passive"))
      (node (ref "R23") (pin "1") (pinfunction "1_1") (pintype "passive"))
      (node (ref "R25") (pin "2") (pinfunction "2_2") (pintype "passive"))
      (node (ref "R30") (pin "2") (pinfunction "2_2") (pintype "passive"))
      (node (ref "U4") (pin "14") (pinfunction "VOS_14") (pintype "input"))
    )
    (net (code "29") (name "Net-(U5-VIN+)") (class "Default")
      (node (ref "C32") (pin "2") (pinfunction "2_2") (pintype "passive"))
      (node (ref "R25") (pin "1") (pinfunction "1_1") (pintype "passive"))
      (node (ref "U5") (pin "1") (pinfunction "VIN+_1") (pintype "input"))
    )
    (net (code "30") (name "Net-(U5-VIN-)") (class "Default")
      (node (ref "C32") (pin "1") (pinfunction "1_1") (pintype "passive"))
      (node (ref "R26") (pin "1") (pinfunction "1_1") (pintype "passive"))
      (node (ref "U5") (pin "2") (pinfunction "VIN-_2") (pintype "input"))
    )
    (net (code "31") (name "Net-(U6-DEF)") (class "Default")
      (node (ref "R46") (pin "2") (pinfunction "2_2") (pintype "passive"))
      (node (ref "U6") (pin "8") (pinfunction "DEF_8") (pintype "input"))
    )
    (net (code "32") (name "Net-(U6-EN)") (class "Default")
      (node (ref "R42") (pin "1") (pinfunction "1_1") (pintype "passive"))
      (node (ref "U6") (pin "13") (pinfunction "EN_13") (pintype "input"))
    )
    (net (code "33") (name "Net-(U6-PG)") (class "Default")
      (node (ref "R45") (pin "1") (pinfunction "1_1") (pintype "passive"))
      (node (ref "U6") (pin "4") (pinfunction "PG_4") (pintype "tri_state"))
    )
    (net (code "34") (name "Net-(U6-SS{slash}TR)") (class "Default")
      (node (ref "C42") (pin "2") (pinfunction "2_2") (pintype "passive"))
      (node (ref "U6") (pin "9") (pinfunction "SS/TR_9") (pintype "input"))
    )
    (net (code "35") (name "Net-(U6-VOS)") (class "Default")
      (node (ref "C38") (pin "2") (pinfunction "2_2") (pintype "passive"))
      (node (ref "C39") (pin "2") (pinfunction "2_2") (pintype "passive"))
      (node (ref "C40") (pin "2") (pinfunction "2_2") (pintype "passive"))
      (node (ref "L2") (pin "2") (pinfunction "2_2") (pintype "passive"))
      (node (ref "R41") (pin "1") (pinfunction "1_1") (pintype "passive"))
      (node (ref "R43") (pin "2") (pinfunction "2_2") (pintype "passive"))
      (node (ref "R45") (pin "2") (pinfunction "2_2") (pintype "passive"))
      (node (ref "U6") (pin "14") (pinfunction "VOS_14") (pintype "input"))
    )
    (net (code "36") (name "Net-(U7-VIN+)") (class "Default")
      (node (ref "C41") (pin "2") (pinfunction "2_2") (pintype "passive"))
      (node (ref "R43") (pin "1") (pinfunction "1_1") (pintype "passive"))
      (node (ref "U7") (pin "1") (pinfunction "VIN+_1") (pintype "input"))
    )
    (net (code "37") (name "Net-(U7-VIN-)") (class "Default")
      (node (ref "C41") (pin "1") (pinfunction "1_1") (pintype "passive"))
      (node (ref "R44") (pin "1") (pinfunction "1_1") (pintype "passive"))
      (node (ref "U7") (pin "2") (pinfunction "VIN-_2") (pintype "input"))
    )
  )
)
